# ProDoc_tracball7.net
KiCad netlist of a schematic drawn in EasyEDA Pro
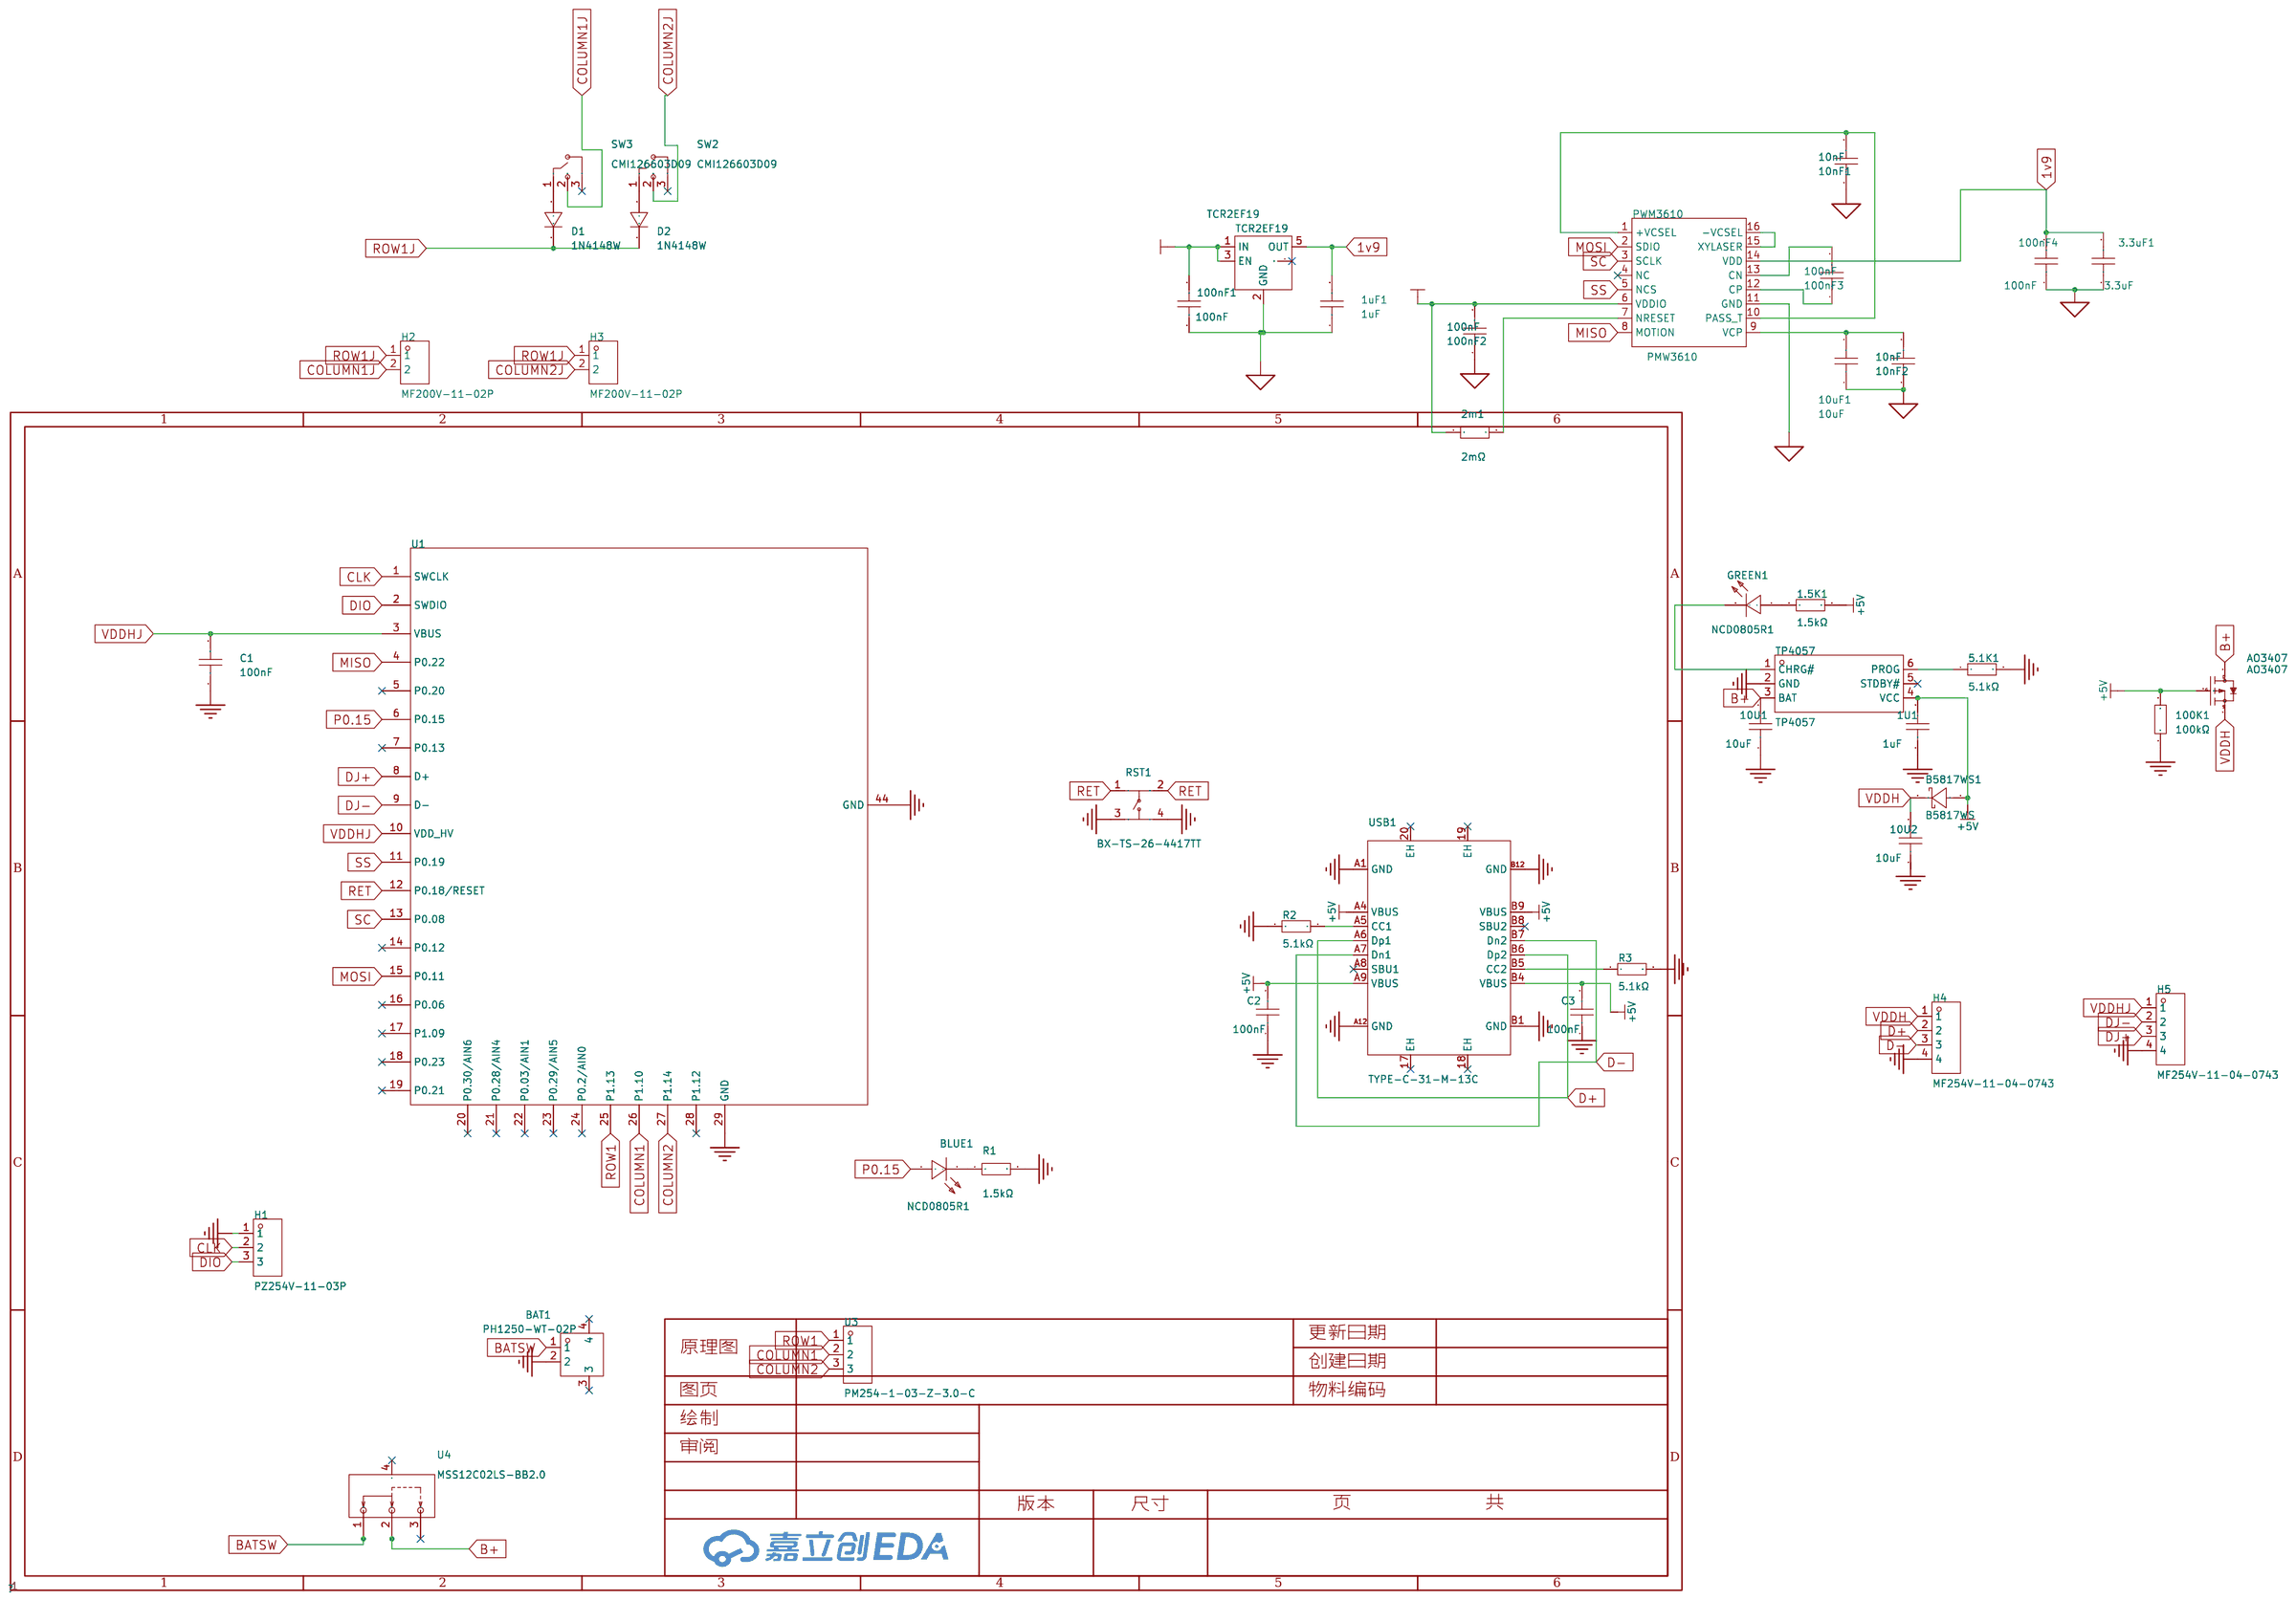
[diagram p0: schematic sheet]

(export (version "E")
  (design (tool "Eeschema 10.0.6"))
  (components
    (comp (ref "1.5K1")
      (value "1.5kΩ")
      (footprint "easyedapro:R0805")
      (description "电阻类型:厚膜电阻;阻值:5.1kΩ;精度:±1%;功率:125mW;最大工作电压:150V;温度系数:±100ppm/°C;")
      (fields
        (field (name "Manufacturer Part") "0805W8F5101T5E")
        (field (name "Manufacturer") "UNI-ROYAL(厚声)")
      )
      (libsource (lib "easyedapro") (part "0805W8F5101T5E"))
    )
    (comp (ref "1U1")
      (value "1uF")
      (footprint "easyedapro:C0603")
      (libsource (lib "easyedapro") (part "CapAcitance"))
    )
    (comp (ref "1uF1")
      (value "1uF")
      (footprint "easyedapro:C0603")
      (fields
        (field (name "Manufacturer Part") "CL21B105KBFNNNE")
        (field (name "Manufacturer") "SAMSUNG(三星)")
      )
      (libsource (lib "easyedapro") (part "CapAcitance"))
    )
    (comp (ref "2m1")
      (value "2mΩ")
      (fields (field (name "Manufacturer Part") "RLM10FTSMR002") (field (name "Manufacturer") "大毅科技"))
      (libsource (lib "easyedapro") (part "电阻"))
    )
    (comp (ref "3.3uF1")
      (value "3.3uF")
      (footprint "easyedapro:C0603")
      (fields (field (name "Manufacturer Part") "0805B335K160NT") (field (name "Manufacturer") "FH(风华)"))
      (libsource (lib "easyedapro") (part "CapAcitance"))
    )
    (comp (ref "5.1K1")
      (value "5.1kΩ")
      (footprint "easyedapro:R0805")
      (description "电阻类型:厚膜电阻;阻值:5.1kΩ;精度:±1%;功率:125mW;最大工作电压:150V;温度系数:±100ppm/°C;")
      (fields
        (field (name "Manufacturer Part") "0805W8F5101T5E")
        (field (name "Manufacturer") "UNI-ROYAL(厚声)")
      )
      (libsource (lib "easyedapro") (part "0805W8F5101T5E"))
    )
    (comp (ref "10nF1")
      (value "10nF")
      (footprint "easyedapro:C0603")
      (fields
        (field (name "Manufacturer Part") "CC0805KRX7R9BB103")
        (field (name "Manufacturer") "YAGEO(国巨)")
      )
      (libsource (lib "easyedapro") (part "CapAcitance"))
    )
    (comp (ref "10nF2")
      (value "10nF")
      (footprint "easyedapro:C0603")
      (fields
        (field (name "Manufacturer Part") "CC0805KRX7R9BB103")
        (field (name "Manufacturer") "YAGEO(国巨)")
      )
      (libsource (lib "easyedapro") (part "CapAcitance"))
    )
    (comp (ref "10U1")
      (value "10uF")
      (footprint "easyedapro:C0603")
      (libsource (lib "easyedapro") (part "CapAcitance"))
    )
    (comp (ref "10U2")
      (value "10uF")
      (footprint "easyedapro:C0603")
      (libsource (lib "easyedapro") (part "CapAcitance"))
    )
    (comp (ref "10uF1")
      (value "10uF")
      (footprint "easyedapro:C0603")
      (fields
        (field (name "Manufacturer Part") "CL21A106KOQNNNE")
        (field (name "Manufacturer") "SAMSUNG(三星)")
      )
      (libsource (lib "easyedapro") (part "CapAcitance"))
    )
    (comp (ref "100K1")
      (value "100kΩ")
      (footprint "easyedapro:R0805")
      (description "电阻类型:厚膜电阻;阻值:5.1kΩ;精度:±1%;功率:125mW;最大工作电压:150V;温度系数:±100ppm/°C;")
      (fields
        (field (name "Manufacturer Part") "0805W8F1003T5E")
        (field (name "Manufacturer") "UNI-ROYAL(厚声)")
      )
      (libsource (lib "easyedapro") (part "0805W8F5101T5E"))
    )
    (comp (ref "100nF1")
      (value "100nF")
      (footprint "easyedapro:C0603")
      (fields (field (name "Manufacturer Part") "0805B104K500NT") (field (name "Manufacturer") "FH(风华)"))
      (libsource (lib "easyedapro") (part "CapAcitance"))
    )
    (comp (ref "100nF2")
      (value "100nF")
      (footprint "easyedapro:C0603")
      (fields (field (name "Manufacturer Part") "0805B104K500NT") (field (name "Manufacturer") "FH(风华)"))
      (libsource (lib "easyedapro") (part "CapAcitance"))
    )
    (comp (ref "100nF3")
      (value "100nF")
      (footprint "easyedapro:C0603")
      (fields (field (name "Manufacturer Part") "0805B104K500NT") (field (name "Manufacturer") "FH(风华)"))
      (libsource (lib "easyedapro") (part "CapAcitance"))
    )
    (comp (ref "100nF4")
      (value "100nF")
      (footprint "easyedapro:C0603")
      (fields (field (name "Manufacturer Part") "0805B104K500NT") (field (name "Manufacturer") "FH(风华)"))
      (libsource (lib "easyedapro") (part "CapAcitance"))
    )
    (comp (ref "AO3407")
      (value "AO3407")
      (footprint "easyedapro:SOT-23-3_L2.9-W1.3-P1.90-LS2.4-BR")
      (fields (field (name "Manufacturer") "Hottech(合科泰)"))
      (libsource (lib "easyedapro") (part "AO3407"))
    )
    (comp (ref "B5817WS1")
      (value "B5817WS")
      (footprint "easyedapro:SOD-323_L1.7-W1.3-LS2.5-FD")
      (description "二极管配置:独立式;正向压降(Vf):450mV@1.0A;直流反向耐压(Vr):20V;平均整流电流(Io):1A;")
      (fields (field (name "Manufacturer") "宏迦橙"))
      (libsource (lib "easyedapro") (part "B5817WS_C7420329"))
    )
    (comp (ref "BAT1")
      (value "PH1250-WT-02P")
      (footprint "easyedapro:CONN-SMD_2P-P1.25-HC-1.25-2PWT")
      (description "插针结构:1x2P;间距:1.25mm;安装方式:卧贴;参考系列:-;总PIN数:2P;排数:1;每排PIN数:2;行距:-;额定电流:-;工作温度范围:-;")
      (fields (field (name "Manufacturer") "HOOYA(皓宇电子)"))
      (libsource (lib "easyedapro") (part "PH1250-WT-02P"))
    )
    (comp (ref "BLUE1")
      (value "NCD0805R1")
      (footprint "easyedapro:LED0805-R-RD")
      (fields (field (name "Manufacturer") "国星光电"))
      (libsource (lib "easyedapro") (part "FC-2012HRK-620D"))
    )
    (comp (ref "C1")
      (value "100nF")
      (footprint "easyedapro:C0603")
      (fields
        (field (name "Manufacturer Part") "CC0603KRX7R9BB104")
        (field (name "Manufacturer") "YAGEO(国巨)")
      )
      (libsource (lib "easyedapro") (part "CapAcitance"))
    )
    (comp (ref "C2")
      (value "100nF")
      (footprint "easyedapro:C0603")
      (libsource (lib "easyedapro") (part "CapAcitance"))
    )
    (comp (ref "C3")
      (value "100nF")
      (footprint "easyedapro:C0603")
      (libsource (lib "easyedapro") (part "CapAcitance"))
    )
    (comp (ref "D1")
      (value "1N4148W")
      (footprint "easyedapro:SOD-123_L2.8-W1.8-LS3.7-RD")
      (description "二极管配置:独立式;正向压降(Vf):1.25V@150mA;直流反向耐压(Vr):100V;平均整流电流(Io):150mA;功率:500mW;反向恢复时间(trr):4ns;")
      (fields (field (name "Manufacturer") "CJ(江苏长电/长晶)"))
      (libsource (lib "easyedapro") (part "1N4148W T4"))
    )
    (comp (ref "D2")
      (value "1N4148W")
      (footprint "easyedapro:SOD-123_L2.8-W1.8-LS3.7-RD")
      (description "二极管配置:独立式;正向压降(Vf):1.25V@150mA;直流反向耐压(Vr):100V;平均整流电流(Io):150mA;功率:500mW;反向恢复时间(trr):4ns;")
      (fields (field (name "Manufacturer") "CJ(江苏长电/长晶)"))
      (libsource (lib "easyedapro") (part "1N4148W T4"))
    )
    (comp (ref "GREEN1")
      (value "NCD0805R1")
      (footprint "easyedapro:LED0805-R-RD")
      (fields (field (name "Manufacturer") "国星光电"))
      (libsource (lib "easyedapro") (part "FC-2012HRK-620D"))
    )
    (comp (ref "H1")
      (value "PZ254V-11-03P")
      (footprint "easyedapro:HDR-TH_3P-P2.54-V-M")
      (fields (field (name "Manufacturer") "XFCN(兴飞)"))
      (libsource (lib "easyedapro") (part "PZ254V-11-03P_C2937625"))
    )
    (comp (ref "H2")
      (value "MF200V-11-02P")
      (footprint "easyedapro:HDR-TH_2P-P2.00-V-F-3")
      (description "插孔结构:1x2P;间距:2mm;行距:-;圆孔/方孔:圆孔;安装类型:直插;排数:单排;总孔位数:2P;额定电流:3A;额定电压:-;插孔方向:顶部;工作温度范围:-40°C~+105°C;")
      (fields (field (name "Manufacturer") "XFCN(兴飞)"))
      (libsource (lib "easyedapro") (part "MF200V-11-02P"))
    )
    (comp (ref "H3")
      (value "MF200V-11-02P")
      (footprint "easyedapro:HDR-TH_2P-P2.00-V-F-3")
      (description "插孔结构:1x2P;间距:2mm;行距:-;圆孔/方孔:圆孔;安装类型:直插;排数:单排;总孔位数:2P;额定电流:3A;额定电压:-;插孔方向:顶部;工作温度范围:-40°C~+105°C;")
      (fields (field (name "Manufacturer") "XFCN(兴飞)"))
      (libsource (lib "easyedapro") (part "MF200V-11-02P"))
    )
    (comp (ref "H4")
      (value "MF254V-11-04-0743")
      (footprint "easyedapro:HDR-TH_4P-P2.54-V-F_MF254V-11-04-0743")
      (fields (field (name "Manufacturer") "XFCN(兴飞)"))
      (libsource (lib "easyedapro") (part "MF254V-11-04-0743"))
    )
    (comp (ref "H5")
      (value "MF254V-11-04-0743")
      (footprint "easyedapro:HDR-TH_4P-P2.54-V-F_MF254V-11-04-0743")
      (fields (field (name "Manufacturer") "XFCN(兴飞)"))
      (libsource (lib "easyedapro") (part "MF254V-11-04-0743"))
    )
    (comp (ref "PWM3610")
      (value "PMW3610")
      (footprint "easyedapro:mylib:PMW3610")
      (libsource (lib "easyedapro") (part "mysymbol_PMW3610"))
    )
    (comp (ref "R1")
      (value "1.5kΩ")
      (footprint "easyedapro:R0805")
      (description "电阻类型:厚膜电阻;阻值:1.5kΩ;精度:±1%;功率:125mW;最大工作电压:150V;温度系数:±100ppm/°C;")
      (fields
        (field (name "Manufacturer Part") "0805W8F1501T5E")
        (field (name "Manufacturer") "UNI-ROYAL(厚声)")
      )
      (libsource (lib "easyedapro") (part "0805W8F1501T5E"))
    )
    (comp (ref "R2")
      (value "5.1kΩ")
      (footprint "easyedapro:R0805")
      (description "电阻类型:厚膜电阻;阻值:5.1kΩ;精度:±1%;功率:125mW;最大工作电压:150V;温度系数:±100ppm/°C;")
      (fields
        (field (name "Manufacturer Part") "0805W8F5101T5E")
        (field (name "Manufacturer") "UNI-ROYAL(厚声)")
      )
      (libsource (lib "easyedapro") (part "0805W8F5101T5E"))
    )
    (comp (ref "R3")
      (value "5.1kΩ")
      (footprint "easyedapro:R0805")
      (description "电阻类型:厚膜电阻;阻值:5.1kΩ;精度:±1%;功率:125mW;最大工作电压:150V;温度系数:±100ppm/°C;")
      (fields
        (field (name "Manufacturer Part") "0805W8F5101T5E")
        (field (name "Manufacturer") "UNI-ROYAL(厚声)")
      )
      (libsource (lib "easyedapro") (part "0805W8F5101T5E"))
    )
    (comp (ref "RST1")
      (value "BX-TS-26-4417TT")
      (footprint "easyedapro:SW-SMD_4P-L5.2-W5.2-P3.70-LS6.5")
      (fields (field (name "Manufacturer") "Bossie(博锡)"))
      (libsource (lib "easyedapro") (part "BX-TS-26-4417TT"))
    )
    (comp (ref "SW2")
      (value "CMI126603D09")
      (footprint "easyedapro:SW-TH_3P-L12.7-W5.6-P5.08")
      (description "类型:微动开关;电路结构:单刀双掷;额定电流(DC):100mA;额定电压(DC):30V;额定电流(AC):-;额定电压(AC):-;机械寿命:3000万次;")
      (fields (field (name "Manufacturer") "Kailh(凯华)"))
      (libsource (lib "easyedapro") (part "CMI126603D09"))
    )
    (comp (ref "SW3")
      (value "CMI126603D09")
      (footprint "easyedapro:SW-TH_3P-L12.7-W5.6-P5.08")
      (description "类型:微动开关;电路结构:单刀双掷;额定电流(DC):100mA;额定电压(DC):30V;额定电流(AC):-;额定电压(AC):-;机械寿命:3000万次;")
      (fields (field (name "Manufacturer") "Kailh(凯华)"))
      (libsource (lib "easyedapro") (part "CMI126603D09"))
    )
    (comp (ref "TCR2EF19")
      (value "TCR2EF19")
      (footprint "easyedapro:Package_TO_SOT_SMD:SOT-23-5")
      (libsource (lib "easyedapro") (part "Regulator_Linear_TLV70218_SOT23-5"))
    )
    (comp (ref "TP4057")
      (value "TP4057")
      (footprint "easyedapro:SOT-23-6_L2.9-W1.6-P0.95-LS2.8-BR")
      (description "电源电压:6.5V;最大充电电流:500mA;电池类型:锂离子/聚合物;电池节数:1;")
      (fields (field (name "Manufacturer") "UMW(友台半导体)"))
      (libsource (lib "easyedapro") (part "TP4057_C725791"))
    )
    (comp (ref "U1")
      (value "N52840")
      (footprint "easyedapro:52840MICRO-v1")
      (libsource (lib "easyedapro") (part "52840micro"))
    )
    (comp (ref "U3")
      (value "PM254-1-03-Z-3.0-C")
      (footprint "easyedapro:HDR-TH_3P-P2.54-V-F-3")
      (fields (field (name "Manufacturer") "HCTL(华灿天禄)"))
      (libsource (lib "easyedapro") (part "PM254-1-03-Z-3.0-C"))
    )
    (comp (ref "U4")
      (value "MSS12C02LS-BB2.0")
      (footprint "easyedapro:SW-SMD_MSS12C02LS-HB2.0-1")
      (description "电路结构:单刀双掷;安装方式:立贴;开关颜色:-;额定电流(DC):100mA;额定电压(DC):12V;额定电流(AC):-;额定电压(AC):-;机械寿命:1万次;")
      (fields (field (name "Manufacturer") "SHOU HAN(首韩)"))
      (libsource (lib "easyedapro") (part "MSS12C02LS-BB2.0"))
    )
    (comp (ref "USB1")
      (value "TYPE-C-31-M-13C")
      (footprint "easyedapro:USB-C-SMD_TYPE-C-31-M-13C")
      (description "连接器类型:Type-C;标准:-;公母:母;端口数量:1;触点数量:16P;安装方式:沉板;额定电流 - 电源:5A;工作温度范围:-30°C~+80°C;")
      (fields (field (name "Manufacturer") "韩国韩荣"))
      (libsource (lib "easyedapro") (part "TYPE-C-31-M-13C"))
    )
  )
  (nets
    (net (code "1") (name "+5V") (class "Default")
      (node (ref "1.5K1") (pin "2") (pinfunction "2_2") (pintype "input"))
      (node (ref "100K1") (pin "2") (pinfunction "2_2") (pintype "input"))
      (node (ref "1U1") (pin "2") (pinfunction "2_2") (pintype "input"))
      (node (ref "AO3407") (pin "1") (pinfunction "G_1") (pintype "unspecified"))
      (node (ref "B5817WS1") (pin "1") (pinfunction "A_1") (pintype "unspecified"))
      (node (ref "C2") (pin "2") (pinfunction "2_2") (pintype "input"))
      (node (ref "C3") (pin "2") (pinfunction "2_2") (pintype "input"))
      (node (ref "TP4057") (pin "4") (pinfunction "VCC_4") (pintype "unspecified"))
      (node (ref "USB1") (pin "A4") (pinfunction "VBUS_A4") (pintype "unspecified"))
      (node (ref "USB1") (pin "A9") (pinfunction "VBUS_A9") (pintype "unspecified"))
      (node (ref "USB1") (pin "B4") (pinfunction "VBUS_B4") (pintype "unspecified"))
      (node (ref "USB1") (pin "B9") (pinfunction "VBUS_B9") (pintype "unspecified"))
    )
    (net (code "2") (name "1v9") (class "Default")
      (node (ref "100nF4") (pin "2") (pinfunction "2_2") (pintype "input"))
      (node (ref "1uF1") (pin "2") (pinfunction "2_2") (pintype "input"))
      (node (ref "3.3uF1") (pin "2") (pinfunction "2_2") (pintype "input"))
      (node (ref "PWM3610") (pin "14") (pinfunction "VDD_14") (pintype "unspecified"))
      (node (ref "TCR2EF19") (pin "5") (pinfunction "OUT_5") (pintype "unspecified"))
    )
    (net (code "3") (name "B+") (class "Default")
      (node (ref "10U1") (pin "2") (pinfunction "2_2") (pintype "input"))
      (node (ref "AO3407") (pin "3") (pinfunction "D_3") (pintype "unspecified"))
      (node (ref "TP4057") (pin "3") (pinfunction "BAT_3") (pintype "unspecified"))
      (node (ref "U4") (pin "2") (pinfunction "2_2") (pintype "unspecified"))
    )
    (net (code "4") (name "BATSW") (class "Default")
      (node (ref "BAT1") (pin "1") (pinfunction "1_1") (pintype "unspecified"))
      (node (ref "U4") (pin "1") (pinfunction "1_1") (pintype "unspecified"))
    )
    (net (code "5") (name "CLK") (class "Default")
      (node (ref "H1") (pin "2") (pinfunction "2_2") (pintype "unspecified"))
      (node (ref "U1") (pin "1") (pinfunction "SWCLK_1") (pintype "input"))
    )
    (net (code "6") (name "COLUMN1") (class "Default")
      (node (ref "U1") (pin "26") (pinfunction "P1.10_26") (pintype "input"))
      (node (ref "U3") (pin "2") (pinfunction "2_2") (pintype "unspecified"))
    )
    (net (code "7") (name "COLUMN1J") (class "Default")
      (node (ref "H2") (pin "2") (pinfunction "2_2") (pintype "unspecified"))
      (node (ref "SW3") (pin "2") (pinfunction "2_2") (pintype "unspecified"))
    )
    (net (code "8") (name "COLUMN2") (class "Default")
      (node (ref "U1") (pin "27") (pinfunction "P1.14_27") (pintype "input"))
      (node (ref "U3") (pin "3") (pinfunction "3_3") (pintype "unspecified"))
    )
    (net (code "9") (name "COLUMN2J") (class "Default")
      (node (ref "H3") (pin "2") (pinfunction "2_2") (pintype "unspecified"))
      (node (ref "SW2") (pin "2") (pinfunction "2_2") (pintype "unspecified"))
    )
    (net (code "10") (name "D+") (class "Default")
      (node (ref "H4") (pin "2") (pinfunction "2_2") (pintype "unspecified"))
      (node (ref "USB1") (pin "A6") (pinfunction "Dp1_A6") (pintype "unspecified"))
      (node (ref "USB1") (pin "B6") (pinfunction "Dp2_B6") (pintype "unspecified"))
    )
    (net (code "11") (name "D-") (class "Default")
      (node (ref "H4") (pin "3") (pinfunction "3_3") (pintype "unspecified"))
      (node (ref "USB1") (pin "A7") (pinfunction "Dn1_A7") (pintype "unspecified"))
      (node (ref "USB1") (pin "B7") (pinfunction "Dn2_B7") (pintype "unspecified"))
    )
    (net (code "12") (name "DIO") (class "Default")
      (node (ref "H1") (pin "3") (pinfunction "3_3") (pintype "unspecified"))
      (node (ref "U1") (pin "2") (pinfunction "SWDIO_2") (pintype "input"))
    )
    (net (code "13") (name "DJ+") (class "Default")
      (node (ref "H5") (pin "3") (pinfunction "3_3") (pintype "unspecified"))
      (node (ref "U1") (pin "8") (pinfunction "D+_8") (pintype "input"))
    )
    (net (code "14") (name "DJ-") (class "Default")
      (node (ref "H5") (pin "2") (pinfunction "2_2") (pintype "unspecified"))
      (node (ref "U1") (pin "9") (pinfunction "D-_9") (pintype "input"))
    )
    (net (code "15") (name "GND") (class "Default")
      (node (ref "100K1") (pin "1") (pinfunction "1_1") (pintype "input"))
      (node (ref "100nF1") (pin "1") (pinfunction "1_1") (pintype "input"))
      (node (ref "100nF2") (pin "1") (pinfunction "1_1") (pintype "input"))
      (node (ref "100nF4") (pin "1") (pinfunction "1_1") (pintype "input"))
      (node (ref "10U1") (pin "1") (pinfunction "1_1") (pintype "input"))
      (node (ref "10U2") (pin "1") (pinfunction "1_1") (pintype "input"))
      (node (ref "10nF1") (pin "1") (pinfunction "1_1") (pintype "input"))
      (node (ref "10nF2") (pin "1") (pinfunction "1_1") (pintype "input"))
      (node (ref "10uF1") (pin "1") (pinfunction "1_1") (pintype "input"))
      (node (ref "1U1") (pin "1") (pinfunction "1_1") (pintype "input"))
      (node (ref "1uF1") (pin "1") (pinfunction "1_1") (pintype "input"))
      (node (ref "3.3uF1") (pin "1") (pinfunction "1_1") (pintype "input"))
      (node (ref "5.1K1") (pin "2") (pinfunction "2_2") (pintype "input"))
      (node (ref "BAT1") (pin "2") (pinfunction "2_2") (pintype "unspecified"))
      (node (ref "C1") (pin "1") (pinfunction "1_1") (pintype "input"))
      (node (ref "C2") (pin "1") (pinfunction "1_1") (pintype "input"))
      (node (ref "C3") (pin "1") (pinfunction "1_1") (pintype "input"))
      (node (ref "H1") (pin "1") (pinfunction "1_1") (pintype "unspecified"))
      (node (ref "H4") (pin "4") (pinfunction "4_4") (pintype "unspecified"))
      (node (ref "H5") (pin "4") (pinfunction "4_4") (pintype "unspecified"))
      (node (ref "PWM3610") (pin "11") (pinfunction "GND_11") (pintype "input"))
      (node (ref "R1") (pin "2") (pinfunction "2_2") (pintype "input"))
      (node (ref "R2") (pin "1") (pinfunction "1_1") (pintype "input"))
      (node (ref "R3") (pin "2") (pinfunction "2_2") (pintype "input"))
      (node (ref "RST1") (pin "3") (pinfunction "3_3") (pintype "unspecified"))
      (node (ref "RST1") (pin "4") (pinfunction "4_4") (pintype "unspecified"))
      (node (ref "TCR2EF19") (pin "2") (pinfunction "GND_2") (pintype "unspecified"))
      (node (ref "TP4057") (pin "2") (pinfunction "GND_2") (pintype "unspecified"))
      (node (ref "U1") (pin "29") (pinfunction "GND_29") (pintype "input"))
      (node (ref "U1") (pin "44") (pinfunction "GND_44") (pintype "input"))
      (node (ref "USB1") (pin "A1") (pinfunction "GND_A1") (pintype "unspecified"))
      (node (ref "USB1") (pin "A12") (pinfunction "GND_A12") (pintype "unspecified"))
      (node (ref "USB1") (pin "B1") (pinfunction "GND_B1") (pintype "unspecified"))
      (node (ref "USB1") (pin "B12") (pinfunction "GND_B12") (pintype "unspecified"))
    )
    (net (code "16") (name "MISO") (class "Default")
      (node (ref "PWM3610") (pin "8") (pinfunction "MOTION_8") (pintype "output"))
      (node (ref "U1") (pin "4") (pinfunction "P0.22_4") (pintype "input"))
    )
    (net (code "17") (name "MOSI") (class "Default")
      (node (ref "PWM3610") (pin "2") (pinfunction "SDIO_2") (pintype "bidirectional"))
      (node (ref "U1") (pin "15") (pinfunction "P0.11_15") (pintype "input"))
    )
    (net (code "18") (name "Net-(BLUE1--)") (class "Default")
      (node (ref "BLUE1") (pin "2") (pinfunction "-_2") (pintype "unspecified"))
      (node (ref "R1") (pin "1") (pinfunction "1_1") (pintype "input"))
    )
    (net (code "19") (name "Net-(D1-A)") (class "Default")
      (node (ref "D1") (pin "2") (pinfunction "A_2") (pintype "unspecified"))
      (node (ref "SW3") (pin "1") (pinfunction "1_1") (pintype "unspecified"))
    )
    (net (code "20") (name "Net-(D2-A)") (class "Default")
      (node (ref "D2") (pin "2") (pinfunction "A_2") (pintype "unspecified"))
      (node (ref "SW2") (pin "1") (pinfunction "1_1") (pintype "unspecified"))
    )
    (net (code "21") (name "Net-(GREEN1-+)") (class "Default")
      (node (ref "1.5K1") (pin "1") (pinfunction "1_1") (pintype "input"))
      (node (ref "GREEN1") (pin "1") (pinfunction "+_1") (pintype "unspecified"))
    )
    (net (code "22") (name "Net-(GREEN1--)") (class "Default")
      (node (ref "GREEN1") (pin "2") (pinfunction "-_2") (pintype "unspecified"))
      (node (ref "TP4057") (pin "1") (pinfunction "CHRG#_1") (pintype "unspecified"))
    )
    (net (code "23") (name "Net-(PWM3610-+VCSEL)") (class "Default")
      (node (ref "10nF1") (pin "2") (pinfunction "2_2") (pintype "input"))
      (node (ref "PWM3610") (pin "1") (pinfunction "+VCSEL_1") (pintype "input"))
      (node (ref "PWM3610") (pin "10") (pinfunction "PASS_T_10") (pintype "unspecified"))
    )
    (net (code "24") (name "Net-(PWM3610--VCSEL)") (class "Default")
      (node (ref "PWM3610") (pin "15") (pinfunction "XYLASER_15") (pintype "input"))
      (node (ref "PWM3610") (pin "16") (pinfunction "-VCSEL_16") (pintype "unspecified"))
    )
    (net (code "25") (name "Net-(PWM3610-CN)") (class "Default")
      (node (ref "100nF3") (pin "2") (pinfunction "2_2") (pintype "input"))
      (node (ref "PWM3610") (pin "13") (pinfunction "CN_13") (pintype "unspecified"))
    )
    (net (code "26") (name "Net-(PWM3610-CP)") (class "Default")
      (node (ref "100nF3") (pin "1") (pinfunction "1_1") (pintype "input"))
      (node (ref "PWM3610") (pin "12") (pinfunction "CP_12") (pintype "unspecified"))
    )
    (net (code "27") (name "Net-(PWM3610-NRESET)") (class "Default")
      (node (ref "2m1") (pin "2") (pinfunction "2_2") (pintype "input"))
      (node (ref "PWM3610") (pin "7") (pinfunction "NRESET_7") (pintype "input"))
    )
    (net (code "28") (name "Net-(PWM3610-VCP)") (class "Default")
      (node (ref "10nF2") (pin "2") (pinfunction "2_2") (pintype "input"))
      (node (ref "10uF1") (pin "2") (pinfunction "2_2") (pintype "input"))
      (node (ref "PWM3610") (pin "9") (pinfunction "VCP_9") (pintype "unspecified"))
    )
    (net (code "29") (name "Net-(TP4057-PROG)") (class "Default")
      (node (ref "5.1K1") (pin "1") (pinfunction "1_1") (pintype "input"))
      (node (ref "TP4057") (pin "6") (pinfunction "PROG_6") (pintype "unspecified"))
    )
    (net (code "30") (name "Net-(USB1-CC1)") (class "Default")
      (node (ref "R2") (pin "2") (pinfunction "2_2") (pintype "input"))
      (node (ref "USB1") (pin "A5") (pinfunction "CC1_A5") (pintype "unspecified"))
    )
    (net (code "31") (name "Net-(USB1-CC2)") (class "Default")
      (node (ref "R3") (pin "1") (pinfunction "1_1") (pintype "input"))
      (node (ref "USB1") (pin "B5") (pinfunction "CC2_B5") (pintype "unspecified"))
    )
    (net (code "32") (name "P0.15") (class "Default")
      (node (ref "BLUE1") (pin "1") (pinfunction "+_1") (pintype "unspecified"))
      (node (ref "U1") (pin "6") (pinfunction "P0.15_6") (pintype "input"))
    )
    (net (code "33") (name "RET") (class "Default")
      (node (ref "RST1") (pin "1") (pinfunction "1_1") (pintype "unspecified"))
      (node (ref "RST1") (pin "2") (pinfunction "2_2") (pintype "unspecified"))
      (node (ref "U1") (pin "12") (pinfunction "P0.18/RESET_12") (pintype "input"))
    )
    (net (code "34") (name "ROW1") (class "Default")
      (node (ref "U1") (pin "25") (pinfunction "P1.13_25") (pintype "input"))
      (node (ref "U3") (pin "1") (pinfunction "1_1") (pintype "unspecified"))
    )
    (net (code "35") (name "ROW1J") (class "Default")
      (node (ref "D1") (pin "1") (pinfunction "K_1") (pintype "unspecified"))
      (node (ref "D2") (pin "1") (pinfunction "K_1") (pintype "unspecified"))
      (node (ref "H2") (pin "1") (pinfunction "1_1") (pintype "unspecified"))
      (node (ref "H3") (pin "1") (pinfunction "1_1") (pintype "unspecified"))
    )
    (net (code "36") (name "SC") (class "Default")
      (node (ref "PWM3610") (pin "3") (pinfunction "SCLK_3") (pintype "input"))
      (node (ref "U1") (pin "13") (pinfunction "P0.08_13") (pintype "input"))
    )
    (net (code "37") (name "SS") (class "Default")
      (node (ref "PWM3610") (pin "5") (pinfunction "NCS_5") (pintype "input"))
      (node (ref "U1") (pin "11") (pinfunction "P0.19_11") (pintype "input"))
    )
    (net (code "38") (name "VCC_EXT") (class "Default")
      (node (ref "100nF1") (pin "2") (pinfunction "2_2") (pintype "input"))
      (node (ref "100nF2") (pin "2") (pinfunction "2_2") (pintype "input"))
      (node (ref "2m1") (pin "1") (pinfunction "1_1") (pintype "input"))
      (node (ref "PWM3610") (pin "6") (pinfunction "VDDIO_6") (pintype "input"))
      (node (ref "TCR2EF19") (pin "1") (pinfunction "IN_1") (pintype "unspecified"))
      (node (ref "TCR2EF19") (pin "3") (pinfunction "EN_3") (pintype "input"))
    )
    (net (code "39") (name "VDDH") (class "Default")
      (node (ref "10U2") (pin "2") (pinfunction "2_2") (pintype "input"))
      (node (ref "AO3407") (pin "2") (pinfunction "S_2") (pintype "unspecified"))
      (node (ref "B5817WS1") (pin "2") (pinfunction "K_2") (pintype "unspecified"))
      (node (ref "H4") (pin "1") (pinfunction "1_1") (pintype "unspecified"))
    )
    (net (code "40") (name "VDDHJ") (class "Default")
      (node (ref "C1") (pin "2") (pinfunction "2_2") (pintype "input"))
      (node (ref "H5") (pin "1") (pinfunction "1_1") (pintype "unspecified"))
      (node (ref "U1") (pin "10") (pinfunction "VDD_HV_10") (pintype "input"))
      (node (ref "U1") (pin "3") (pinfunction "VBUS_3") (pintype "input"))
    )
    (net (code "41") (name "unconnected-(BAT1-Pad3)") (class "Default")
      (node (ref "BAT1") (pin "3") (pinfunction "3_3") (pintype "unspecified+no_connect"))
    )
    (net (code "42") (name "unconnected-(BAT1-Pad4)") (class "Default")
      (node (ref "BAT1") (pin "4") (pinfunction "4_4") (pintype "unspecified+no_connect"))
    )
    (net (code "43") (name "unconnected-(PWM3610-NC-Pad4)") (class "Default")
      (node (ref "PWM3610") (pin "4") (pinfunction "NC_4") (pintype "unspecified+no_connect"))
    )
    (net (code "44") (name "unconnected-(SW2-Pad3)") (class "Default")
      (node (ref "SW2") (pin "3") (pinfunction "3_3") (pintype "unspecified+no_connect"))
    )
    (net (code "45") (name "unconnected-(SW3-Pad3)") (class "Default")
      (node (ref "SW3") (pin "3") (pinfunction "3_3") (pintype "unspecified+no_connect"))
    )
    (net (code "46") (name "unconnected-(TCR2EF19-NC-Pad4)") (class "Default")
      (node (ref "TCR2EF19") (pin "4") (pinfunction "NC_4") (pintype "unspecified+no_connect"))
    )
    (net (code "47") (name "unconnected-(TP4057-STDBY#-Pad5)") (class "Default")
      (node (ref "TP4057") (pin "5") (pinfunction "STDBY#_5") (pintype "unspecified+no_connect"))
    )
    (net (code "48") (name "unconnected-(U1-P0.2{slash}AIN0-Pad24)") (class "Default")
      (node (ref "U1") (pin "24") (pinfunction "P0.2/AIN0_24") (pintype "input+no_connect"))
    )
    (net (code "49") (name "unconnected-(U1-P0.03{slash}AIN1-Pad22)") (class "Default")
      (node (ref "U1") (pin "22") (pinfunction "P0.03/AIN1_22") (pintype "input+no_connect"))
    )
    (net (code "50") (name "unconnected-(U1-P0.06-Pad16)") (class "Default")
      (node (ref "U1") (pin "16") (pinfunction "P0.06_16") (pintype "input+no_connect"))
    )
    (net (code "51") (name "unconnected-(U1-P0.12-Pad14)") (class "Default")
      (node (ref "U1") (pin "14") (pinfunction "P0.12_14") (pintype "input+no_connect"))
    )
    (net (code "52") (name "unconnected-(U1-P0.13-Pad7)") (class "Default")
      (node (ref "U1") (pin "7") (pinfunction "P0.13_7") (pintype "input+no_connect"))
    )
    (net (code "53") (name "unconnected-(U1-P0.20-Pad5)") (class "Default")
      (node (ref "U1") (pin "5") (pinfunction "P0.20_5") (pintype "input+no_connect"))
    )
    (net (code "54") (name "unconnected-(U1-P0.21-Pad19)") (class "Default")
      (node (ref "U1") (pin "19") (pinfunction "P0.21_19") (pintype "input+no_connect"))
    )
    (net (code "55") (name "unconnected-(U1-P0.23-Pad18)") (class "Default")
      (node (ref "U1") (pin "18") (pinfunction "P0.23_18") (pintype "input+no_connect"))
    )
    (net (code "56") (name "unconnected-(U1-P0.28{slash}AIN4-Pad21)") (class "Default")
      (node (ref "U1") (pin "21") (pinfunction "P0.28/AIN4_21") (pintype "input+no_connect"))
    )
    (net (code "57") (name "unconnected-(U1-P0.29{slash}AIN5-Pad23)") (class "Default")
      (node (ref "U1") (pin "23") (pinfunction "P0.29/AIN5_23") (pintype "input+no_connect"))
    )
    (net (code "58") (name "unconnected-(U1-P0.30{slash}AIN6-Pad20)") (class "Default")
      (node (ref "U1") (pin "20") (pinfunction "P0.30/AIN6_20") (pintype "input+no_connect"))
    )
    (net (code "59") (name "unconnected-(U1-P1.09-Pad17)") (class "Default")
      (node (ref "U1") (pin "17") (pinfunction "P1.09_17") (pintype "input+no_connect"))
    )
    (net (code "60") (name "unconnected-(U1-P1.12-Pad28)") (class "Default")
      (node (ref "U1") (pin "28") (pinfunction "P1.12_28") (pintype "input+no_connect"))
    )
    (net (code "61") (name "unconnected-(U4-Pad3)") (class "Default")
      (node (ref "U4") (pin "3") (pinfunction "3_3") (pintype "unspecified+no_connect"))
    )
    (net (code "62") (name "unconnected-(U4-Pad4)") (class "Default")
      (node (ref "U4") (pin "4") (pinfunction "4_4") (pintype "unspecified+no_connect"))
    )
    (net (code "63") (name "unconnected-(USB1-EH-Pad17)") (class "Default")
      (node (ref "USB1") (pin "17") (pinfunction "EH_17") (pintype "unspecified+no_connect"))
    )
    (net (code "64") (name "unconnected-(USB1-EH-Pad18)") (class "Default")
      (node (ref "USB1") (pin "18") (pinfunction "EH_18") (pintype "unspecified+no_connect"))
    )
    (net (code "65") (name "unconnected-(USB1-EH-Pad19)") (class "Default")
      (node (ref "USB1") (pin "19") (pinfunction "EH_19") (pintype "unspecified+no_connect"))
    )
    (net (code "66") (name "unconnected-(USB1-EH-Pad20)") (class "Default")
      (node (ref "USB1") (pin "20") (pinfunction "EH_20") (pintype "unspecified+no_connect"))
    )
    (net (code "67") (name "unconnected-(USB1-SBU1-PadA8)") (class "Default")
      (node (ref "USB1") (pin "A8") (pinfunction "SBU1_A8") (pintype "unspecified+no_connect"))
    )
    (net (code "68") (name "unconnected-(USB1-SBU2-PadB8)") (class "Default")
      (node (ref "USB1") (pin "B8") (pinfunction "SBU2_B8") (pintype "unspecified+no_connect"))
    )
  )
)
